# v6_net.net
KiCad netlist of a schematic drawn in Altium Designer
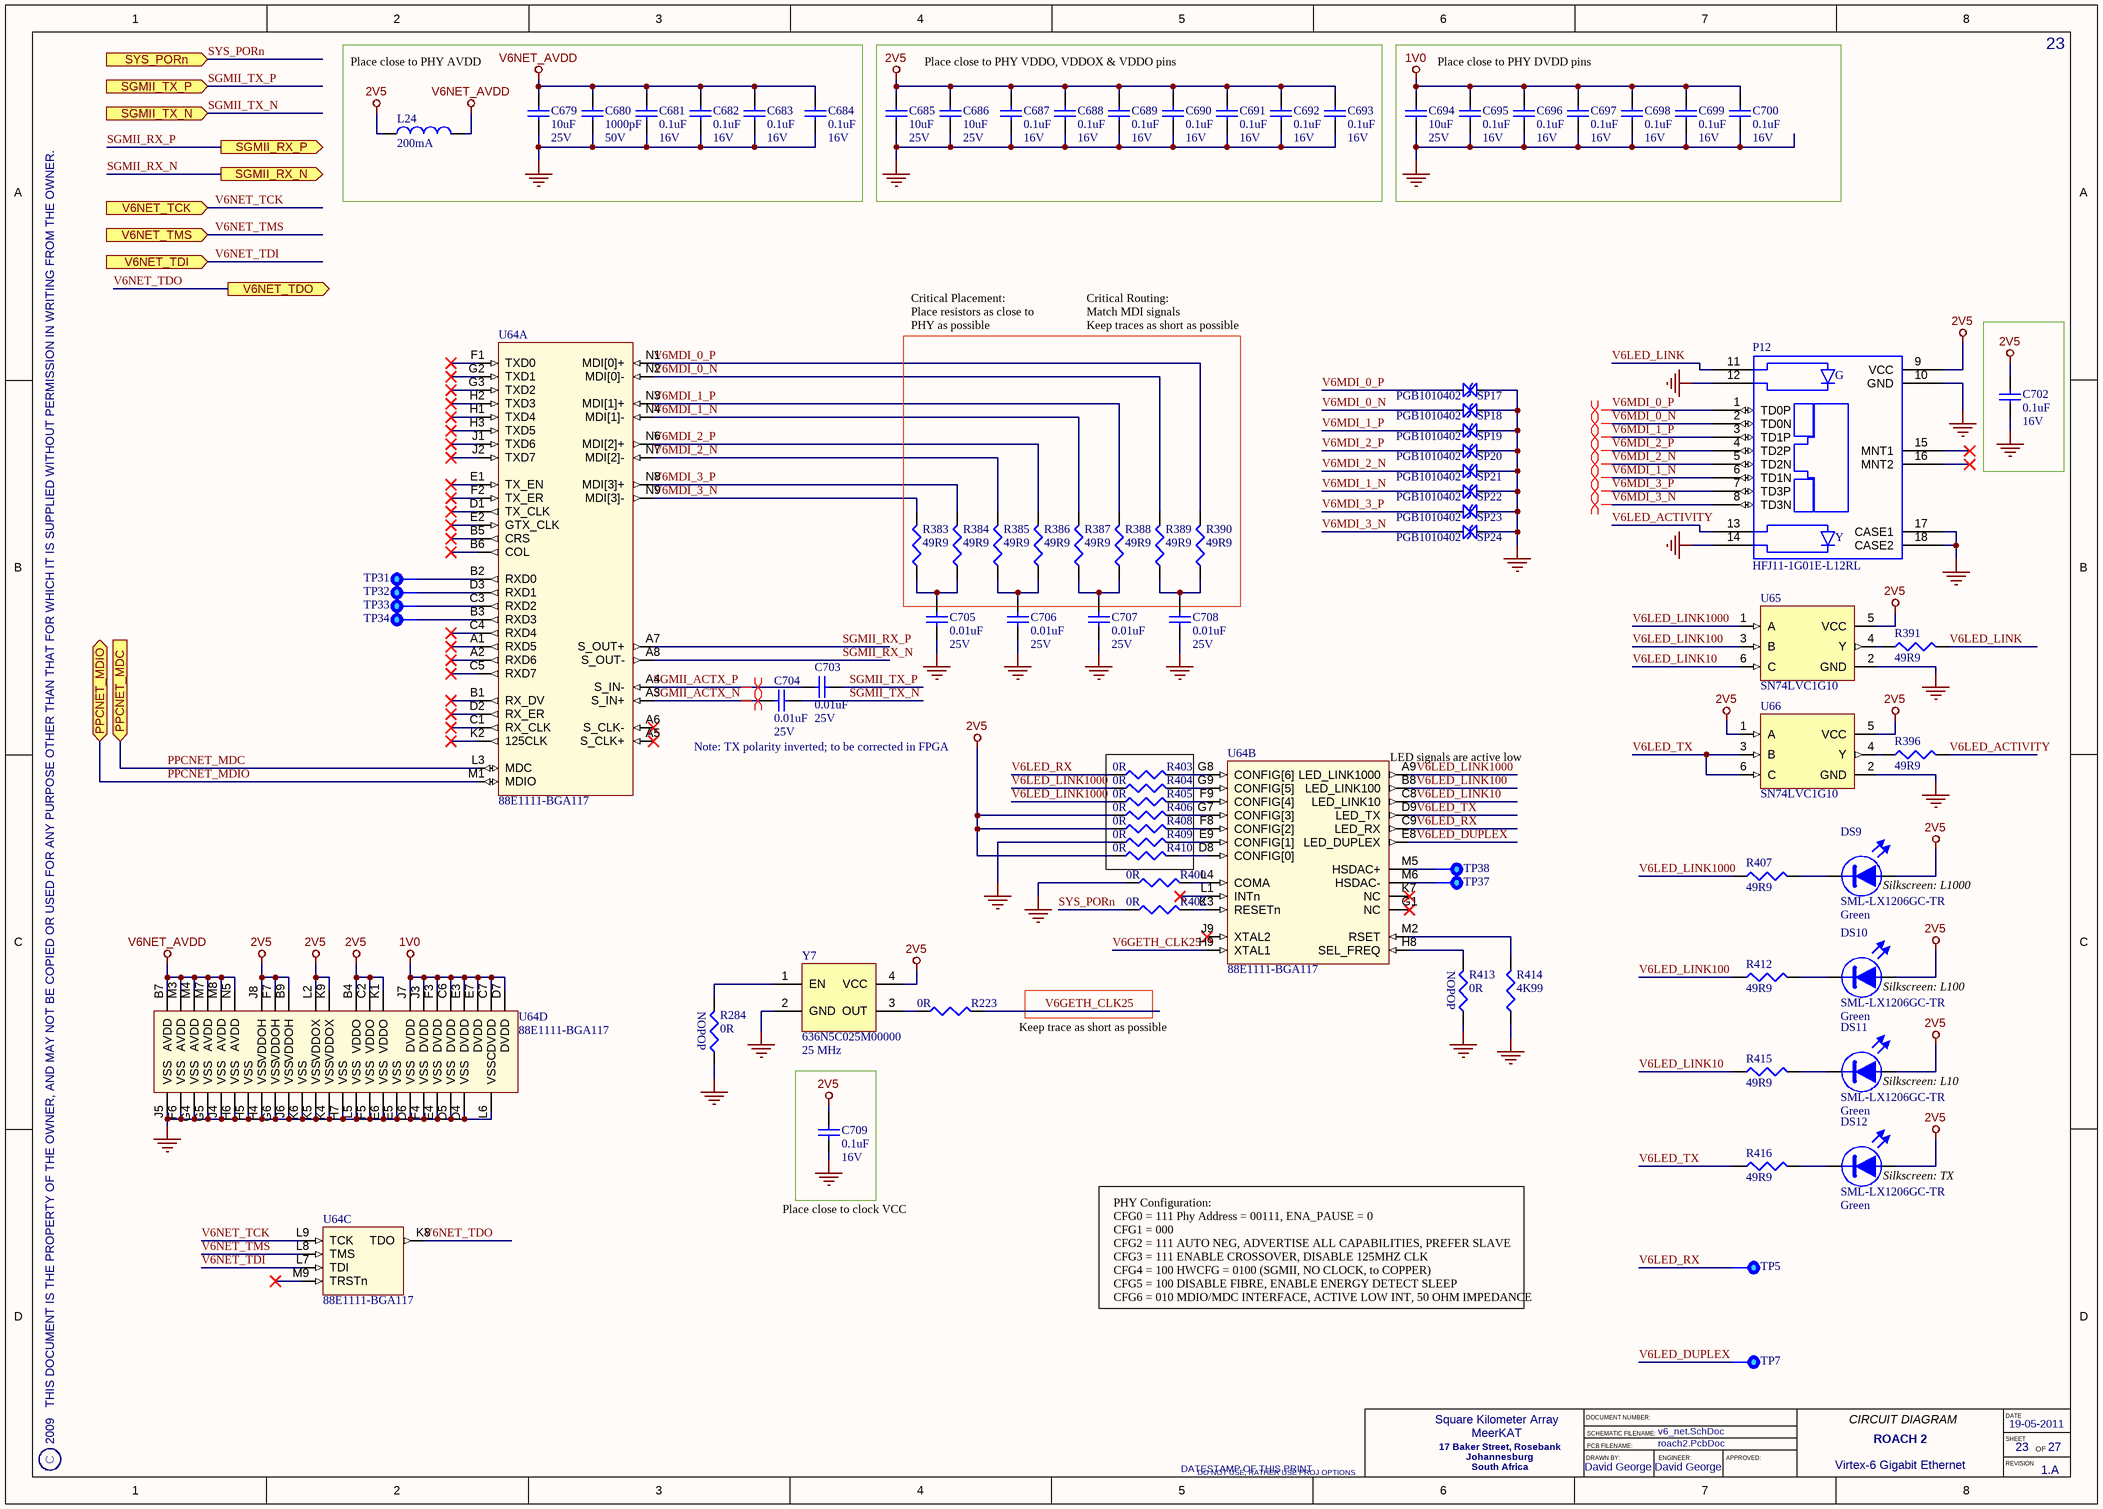
[diagram p0: v6_net.SchDoc]

(export (version "E")
  (design (tool "Eeschema 10.0.6"))
  (components
    (comp (ref "C679")
      (value "10uF")
      (footprint "CAPC3225X200L")
      (description "10uF, Ceramic Capacitor")
      (fields
        (field (name "RATING") "25V")
        (field (name "MANUFACTURER") "MURATA")
        (field (name "PARTNUM") "GRM32DR61E106KA12L")
      )
      (libsource (lib "altium_db") (part "CapStd"))
    )
    (comp (ref "C680")
      (value "1000pF")
      (footprint "CAPC1005X55L")
      (description "1000pF, Ceramic Capacitor")
      (fields
        (field (name "RATING") "50V")
        (field (name "MANUFACTURER") "MURATA")
        (field (name "PARTNUM") "GRM155R61H102KA01D")
      )
      (libsource (lib "altium_db") (part "CapStd"))
    )
    (comp (ref "C681")
      (value "0.1uF")
      (footprint "CAPC1005X60L")
      (description "0.1uF, Ceramic Capacitor")
      (fields
        (field (name "RATING") "16V")
        (field (name "MANUFACTURER") "VENKEL")
        (field (name "PARTNUM") "C0402X7R160-104KN")
      )
      (libsource (lib "altium_db") (part "CapStd"))
    )
    (comp (ref "C682")
      (value "0.1uF")
      (footprint "CAPC1005X60L")
      (description "0.1uF, Ceramic Capacitor")
      (fields
        (field (name "RATING") "16V")
        (field (name "MANUFACTURER") "VENKEL")
        (field (name "PARTNUM") "C0402X7R160-104KN")
      )
      (libsource (lib "altium_db") (part "CapStd"))
    )
    (comp (ref "C683")
      (value "0.1uF")
      (footprint "CAPC1005X60L")
      (description "0.1uF, Ceramic Capacitor")
      (fields
        (field (name "RATING") "16V")
        (field (name "MANUFACTURER") "VENKEL")
        (field (name "PARTNUM") "C0402X7R160-104KN")
      )
      (libsource (lib "altium_db") (part "CapStd"))
    )
    (comp (ref "C684")
      (value "0.1uF")
      (footprint "CAPC1005X60L")
      (description "0.1uF, Ceramic Capacitor")
      (fields
        (field (name "RATING") "16V")
        (field (name "MANUFACTURER") "VENKEL")
        (field (name "PARTNUM") "C0402X7R160-104KN")
      )
      (libsource (lib "altium_db") (part "CapStd"))
    )
    (comp (ref "C685")
      (value "10uF")
      (footprint "CAPC3225X200L")
      (description "10uF, Ceramic Capacitor")
      (fields
        (field (name "RATING") "25V")
        (field (name "MANUFACTURER") "MURATA")
        (field (name "PARTNUM") "GRM32DR61E106KA12L")
      )
      (libsource (lib "altium_db") (part "CapStd"))
    )
    (comp (ref "C686")
      (value "10uF")
      (footprint "CAPC3225X200L")
      (description "10uF, Ceramic Capacitor")
      (fields
        (field (name "RATING") "25V")
        (field (name "MANUFACTURER") "MURATA")
        (field (name "PARTNUM") "GRM32DR61E106KA12L")
      )
      (libsource (lib "altium_db") (part "CapStd"))
    )
    (comp (ref "C687")
      (value "0.1uF")
      (footprint "CAPC1005X60L")
      (description "0.1uF, Ceramic Capacitor")
      (fields
        (field (name "RATING") "16V")
        (field (name "MANUFACTURER") "VENKEL")
        (field (name "PARTNUM") "C0402X7R160-104KN")
      )
      (libsource (lib "altium_db") (part "CapStd"))
    )
    (comp (ref "C688")
      (value "0.1uF")
      (footprint "CAPC1005X60L")
      (description "0.1uF, Ceramic Capacitor")
      (fields
        (field (name "RATING") "16V")
        (field (name "MANUFACTURER") "VENKEL")
        (field (name "PARTNUM") "C0402X7R160-104KN")
      )
      (libsource (lib "altium_db") (part "CapStd"))
    )
    (comp (ref "C689")
      (value "0.1uF")
      (footprint "CAPC1005X60L")
      (description "0.1uF, Ceramic Capacitor")
      (fields
        (field (name "RATING") "16V")
        (field (name "MANUFACTURER") "VENKEL")
        (field (name "PARTNUM") "C0402X7R160-104KN")
      )
      (libsource (lib "altium_db") (part "CapStd"))
    )
    (comp (ref "C690")
      (value "0.1uF")
      (footprint "CAPC1005X60L")
      (description "0.1uF, Ceramic Capacitor")
      (fields
        (field (name "RATING") "16V")
        (field (name "MANUFACTURER") "VENKEL")
        (field (name "PARTNUM") "C0402X7R160-104KN")
      )
      (libsource (lib "altium_db") (part "CapStd"))
    )
    (comp (ref "C691")
      (value "0.1uF")
      (footprint "CAPC1005X60L")
      (description "0.1uF, Ceramic Capacitor")
      (fields
        (field (name "RATING") "16V")
        (field (name "MANUFACTURER") "VENKEL")
        (field (name "PARTNUM") "C0402X7R160-104KN")
      )
      (libsource (lib "altium_db") (part "CapStd"))
    )
    (comp (ref "C692")
      (value "0.1uF")
      (footprint "CAPC1005X60L")
      (description "0.1uF, Ceramic Capacitor")
      (fields
        (field (name "RATING") "16V")
        (field (name "MANUFACTURER") "VENKEL")
        (field (name "PARTNUM") "C0402X7R160-104KN")
      )
      (libsource (lib "altium_db") (part "CapStd"))
    )
    (comp (ref "C693")
      (value "0.1uF")
      (footprint "CAPC1005X60L")
      (description "0.1uF, Ceramic Capacitor")
      (fields
        (field (name "RATING") "16V")
        (field (name "MANUFACTURER") "VENKEL")
        (field (name "PARTNUM") "C0402X7R160-104KN")
      )
      (libsource (lib "altium_db") (part "CapStd"))
    )
    (comp (ref "C694")
      (value "10uF")
      (footprint "CAPC3225X200L")
      (description "10uF, Ceramic Capacitor")
      (fields
        (field (name "RATING") "25V")
        (field (name "MANUFACTURER") "MURATA")
        (field (name "PARTNUM") "GRM32DR61E106KA12L")
      )
      (libsource (lib "altium_db") (part "CapStd"))
    )
    (comp (ref "C695")
      (value "0.1uF")
      (footprint "CAPC1005X60L")
      (description "0.1uF, Ceramic Capacitor")
      (fields
        (field (name "RATING") "16V")
        (field (name "MANUFACTURER") "VENKEL")
        (field (name "PARTNUM") "C0402X7R160-104KN")
      )
      (libsource (lib "altium_db") (part "CapStd"))
    )
    (comp (ref "C696")
      (value "0.1uF")
      (footprint "CAPC1005X60L")
      (description "0.1uF, Ceramic Capacitor")
      (fields
        (field (name "RATING") "16V")
        (field (name "MANUFACTURER") "VENKEL")
        (field (name "PARTNUM") "C0402X7R160-104KN")
      )
      (libsource (lib "altium_db") (part "CapStd"))
    )
    (comp (ref "C697")
      (value "0.1uF")
      (footprint "CAPC1005X60L")
      (description "0.1uF, Ceramic Capacitor")
      (fields
        (field (name "RATING") "16V")
        (field (name "MANUFACTURER") "VENKEL")
        (field (name "PARTNUM") "C0402X7R160-104KN")
      )
      (libsource (lib "altium_db") (part "CapStd"))
    )
    (comp (ref "C698")
      (value "0.1uF")
      (footprint "CAPC1005X60L")
      (description "0.1uF, Ceramic Capacitor")
      (fields
        (field (name "RATING") "16V")
        (field (name "MANUFACTURER") "VENKEL")
        (field (name "PARTNUM") "C0402X7R160-104KN")
      )
      (libsource (lib "altium_db") (part "CapStd"))
    )
    (comp (ref "C699")
      (value "0.1uF")
      (footprint "CAPC1005X60L")
      (description "0.1uF, Ceramic Capacitor")
      (fields
        (field (name "RATING") "16V")
        (field (name "MANUFACTURER") "VENKEL")
        (field (name "PARTNUM") "C0402X7R160-104KN")
      )
      (libsource (lib "altium_db") (part "CapStd"))
    )
    (comp (ref "C700")
      (value "0.1uF")
      (footprint "CAPC1005X60L")
      (description "0.1uF, Ceramic Capacitor")
      (fields
        (field (name "RATING") "16V")
        (field (name "MANUFACTURER") "VENKEL")
        (field (name "PARTNUM") "C0402X7R160-104KN")
      )
      (libsource (lib "altium_db") (part "CapStd"))
    )
    (comp (ref "C702")
      (value "0.1uF")
      (footprint "CAPC1005X60L")
      (description "0.1uF, Ceramic Capacitor")
      (fields
        (field (name "RATING") "16V")
        (field (name "MANUFACTURER") "VENKEL")
        (field (name "PARTNUM") "C0402X7R160-104KN")
      )
      (libsource (lib "altium_db") (part "CapStd"))
    )
    (comp (ref "C703")
      (value "0.01uF")
      (footprint "CAPC1005X55L")
      (description "0.01uF, Ceramic Capacitor")
      (fields
        (field (name "RATING") "25V")
        (field (name "MANUFACTURER") "MURATA")
        (field (name "PARTNUM") "GRM155R71E103KA01D")
      )
      (libsource (lib "altium_db") (part "CapStd"))
    )
    (comp (ref "C704")
      (value "0.01uF")
      (footprint "CAPC1005X55L")
      (description "0.01uF, Ceramic Capacitor")
      (fields
        (field (name "RATING") "25V")
        (field (name "MANUFACTURER") "MURATA")
        (field (name "PARTNUM") "GRM155R71E103KA01D")
      )
      (libsource (lib "altium_db") (part "CapStd"))
    )
    (comp (ref "C705")
      (value "0.01uF")
      (footprint "CAPC1005X55L")
      (description "0.01uF, Ceramic Capacitor")
      (fields
        (field (name "RATING") "25V")
        (field (name "MANUFACTURER") "MURATA")
        (field (name "PARTNUM") "GRM155R71E103KA01D")
      )
      (libsource (lib "altium_db") (part "CapStd"))
    )
    (comp (ref "C706")
      (value "0.01uF")
      (footprint "CAPC1005X55L")
      (description "0.01uF, Ceramic Capacitor")
      (fields
        (field (name "RATING") "25V")
        (field (name "MANUFACTURER") "MURATA")
        (field (name "PARTNUM") "GRM155R71E103KA01D")
      )
      (libsource (lib "altium_db") (part "CapStd"))
    )
    (comp (ref "C707")
      (value "0.01uF")
      (footprint "CAPC1005X55L")
      (description "0.01uF, Ceramic Capacitor")
      (fields
        (field (name "RATING") "25V")
        (field (name "MANUFACTURER") "MURATA")
        (field (name "PARTNUM") "GRM155R71E103KA01D")
      )
      (libsource (lib "altium_db") (part "CapStd"))
    )
    (comp (ref "C708")
      (value "0.01uF")
      (footprint "CAPC1005X55L")
      (description "0.01uF, Ceramic Capacitor")
      (fields
        (field (name "RATING") "25V")
        (field (name "MANUFACTURER") "MURATA")
        (field (name "PARTNUM") "GRM155R71E103KA01D")
      )
      (libsource (lib "altium_db") (part "CapStd"))
    )
    (comp (ref "C709")
      (value "0.1uF")
      (footprint "CAPC1005X60L")
      (description "0.1uF, Ceramic Capacitor")
      (fields
        (field (name "RATING") "16V")
        (field (name "MANUFACTURER") "VENKEL")
        (field (name "PARTNUM") "C0402X7R160-104KN")
      )
      (libsource (lib "altium_db") (part "CapStd"))
    )
    (comp (ref "DS9")
      (value "SML-LX1206GC-TR")
      (footprint "LEDC3216X120N")
      (description "Green, Surface mount, LED, 1206")
      (fields (field (name "COLOUR") "Green") (field (name "MANUFACTURER") "LUMEX"))
      (libsource (lib "altium_db") (part "LEDSTD"))
    )
    (comp (ref "DS10")
      (value "SML-LX1206GC-TR")
      (footprint "LEDC3216X120N")
      (description "Green, Surface mount, LED, 1206")
      (fields (field (name "COLOUR") "Green") (field (name "MANUFACTURER") "LUMEX"))
      (libsource (lib "altium_db") (part "LEDSTD"))
    )
    (comp (ref "DS11")
      (value "SML-LX1206GC-TR")
      (footprint "LEDC3216X120N")
      (description "Green, Surface mount, LED, 1206")
      (fields (field (name "COLOUR") "Green") (field (name "MANUFACTURER") "LUMEX"))
      (libsource (lib "altium_db") (part "LEDSTD"))
    )
    (comp (ref "DS12")
      (value "SML-LX1206GC-TR")
      (footprint "LEDC3216X120N")
      (description "Green, Surface mount, LED, 1206")
      (fields (field (name "COLOUR") "Green") (field (name "MANUFACTURER") "LUMEX"))
      (libsource (lib "altium_db") (part "LEDSTD"))
    )
    (comp (ref "L24")
      (value "600R")
      (footprint "INDC2012X130L")
      (description "600 Ohm, Chip Ferrite Bead")
      (fields
        (field (name "RATING") "200mA")
        (field (name "MANUFACTURER") "Murata")
        (field (name "PARTNUM") "BLM21BD601SN1")
      )
      (libsource (lib "altium_db") (part "IndStd"))
    )
    (comp (ref "P12")
      (value "HFJ11-1G01E-L12RL")
      (footprint "HALO_HFJ11-1G02E-L55")
      (description "RJ45 with Integrated magnetic and dual LEDs")
      (fields (field (name "PARTNUM") "HFJ11-1G01E-L12RL") (field (name "MANUFACTURER") "HALO"))
      (libsource (lib "altium_db") (part "HFJ11-1G02E-L55"))
    )
    (comp (ref "R223")
      (value "0R")
      (footprint "RESC1005X40L")
      (description "0R, 1.1mm x 0.5mm, Thick Film Resistor")
      (fields (field (name "MANUFACTURER") "ROYALOHM") (field (name "PARTNUM") "0402WG00000T1E"))
      (libsource (lib "altium_db") (part "ResStd"))
    )
    (comp (ref "R284")
      (value "0R")
      (footprint "RESC1005X40L")
      (description "0R, 1.1mm x 0.5mm, Thick Film Resistor")
      (fields (field (name "MANUFACTURER") "ROYALOHM") (field (name "PARTNUM") "0402WG00000T1E"))
      (libsource (lib "altium_db") (part "ResStd"))
    )
    (comp (ref "R383")
      (value "49R9")
      (footprint "RESC1005X40L")
      (description "49R9, 1.1mm x 0.5mm, Thick Film Resistor")
      (fields (field (name "MANUFACTURER") "ROYALOHM") (field (name "PARTNUM") "0402WGF499JT1E"))
      (libsource (lib "altium_db") (part "ResStd"))
    )
    (comp (ref "R384")
      (value "49R9")
      (footprint "RESC1005X40L")
      (description "49R9, 1.1mm x 0.5mm, Thick Film Resistor")
      (fields (field (name "MANUFACTURER") "ROYALOHM") (field (name "PARTNUM") "0402WGF499JT1E"))
      (libsource (lib "altium_db") (part "ResStd"))
    )
    (comp (ref "R385")
      (value "49R9")
      (footprint "RESC1005X40L")
      (description "49R9, 1.1mm x 0.5mm, Thick Film Resistor")
      (fields (field (name "MANUFACTURER") "ROYALOHM") (field (name "PARTNUM") "0402WGF499JT1E"))
      (libsource (lib "altium_db") (part "ResStd"))
    )
    (comp (ref "R386")
      (value "49R9")
      (footprint "RESC1005X40L")
      (description "49R9, 1.1mm x 0.5mm, Thick Film Resistor")
      (fields (field (name "MANUFACTURER") "ROYALOHM") (field (name "PARTNUM") "0402WGF499JT1E"))
      (libsource (lib "altium_db") (part "ResStd"))
    )
    (comp (ref "R387")
      (value "49R9")
      (footprint "RESC1005X40L")
      (description "49R9, 1.1mm x 0.5mm, Thick Film Resistor")
      (fields (field (name "MANUFACTURER") "ROYALOHM") (field (name "PARTNUM") "0402WGF499JT1E"))
      (libsource (lib "altium_db") (part "ResStd"))
    )
    (comp (ref "R388")
      (value "49R9")
      (footprint "RESC1005X40L")
      (description "49R9, 1.1mm x 0.5mm, Thick Film Resistor")
      (fields (field (name "MANUFACTURER") "ROYALOHM") (field (name "PARTNUM") "0402WGF499JT1E"))
      (libsource (lib "altium_db") (part "ResStd"))
    )
    (comp (ref "R389")
      (value "49R9")
      (footprint "RESC1005X40L")
      (description "49R9, 1.1mm x 0.5mm, Thick Film Resistor")
      (fields (field (name "MANUFACTURER") "ROYALOHM") (field (name "PARTNUM") "0402WGF499JT1E"))
      (libsource (lib "altium_db") (part "ResStd"))
    )
    (comp (ref "R390")
      (value "49R9")
      (footprint "RESC1005X40L")
      (description "49R9, 1.1mm x 0.5mm, Thick Film Resistor")
      (fields (field (name "MANUFACTURER") "ROYALOHM") (field (name "PARTNUM") "0402WGF499JT1E"))
      (libsource (lib "altium_db") (part "ResStd"))
    )
    (comp (ref "R391")
      (value "49R9")
      (footprint "RESC1005X40L")
      (description "49R9, 1.1mm x 0.5mm, Thick Film Resistor")
      (fields (field (name "MANUFACTURER") "ROYALOHM") (field (name "PARTNUM") "0402WGF499JT1E"))
      (libsource (lib "altium_db") (part "ResStd"))
    )
    (comp (ref "R396")
      (value "49R9")
      (footprint "RESC1005X40L")
      (description "49R9, 1.1mm x 0.5mm, Thick Film Resistor")
      (fields (field (name "MANUFACTURER") "ROYALOHM") (field (name "PARTNUM") "0402WGF499JT1E"))
      (libsource (lib "altium_db") (part "ResStd"))
    )
    (comp (ref "R400")
      (value "0R")
      (footprint "RESC1005X40L")
      (description "0R, 1.1mm x 0.5mm, Thick Film Resistor")
      (fields (field (name "MANUFACTURER") "ROYALOHM") (field (name "PARTNUM") "0402WG00000T1E"))
      (libsource (lib "altium_db") (part "ResStd"))
    )
    (comp (ref "R402")
      (value "0R")
      (footprint "RESC1005X40L")
      (description "0R, 1.1mm x 0.5mm, Thick Film Resistor")
      (fields (field (name "MANUFACTURER") "ROYALOHM") (field (name "PARTNUM") "0402WG00000T1E"))
      (libsource (lib "altium_db") (part "ResStd"))
    )
    (comp (ref "R403")
      (value "0R")
      (footprint "RESC1005X40L")
      (description "0R, 1.1mm x 0.5mm, Thick Film Resistor")
      (fields (field (name "MANUFACTURER") "ROYALOHM") (field (name "PARTNUM") "0402WG00000T1E"))
      (libsource (lib "altium_db") (part "ResStd"))
    )
    (comp (ref "R404")
      (value "0R")
      (footprint "RESC1005X40L")
      (description "0R, 1.1mm x 0.5mm, Thick Film Resistor")
      (fields (field (name "MANUFACTURER") "ROYALOHM") (field (name "PARTNUM") "0402WG00000T1E"))
      (libsource (lib "altium_db") (part "ResStd"))
    )
    (comp (ref "R405")
      (value "0R")
      (footprint "RESC1005X40L")
      (description "0R, 1.1mm x 0.5mm, Thick Film Resistor")
      (fields (field (name "MANUFACTURER") "ROYALOHM") (field (name "PARTNUM") "0402WG00000T1E"))
      (libsource (lib "altium_db") (part "ResStd"))
    )
    (comp (ref "R406")
      (value "0R")
      (footprint "RESC1005X40L")
      (description "0R, 1.1mm x 0.5mm, Thick Film Resistor")
      (fields (field (name "MANUFACTURER") "ROYALOHM") (field (name "PARTNUM") "0402WG00000T1E"))
      (libsource (lib "altium_db") (part "ResStd"))
    )
    (comp (ref "R407")
      (value "49R9")
      (footprint "RESC1005X40L")
      (description "49R9, 1.1mm x 0.5mm, Thick Film Resistor")
      (fields (field (name "MANUFACTURER") "ROYALOHM") (field (name "PARTNUM") "0402WGF499JT1E"))
      (libsource (lib "altium_db") (part "ResStd"))
    )
    (comp (ref "R408")
      (value "0R")
      (footprint "RESC1005X40L")
      (description "0R, 1.1mm x 0.5mm, Thick Film Resistor")
      (fields (field (name "MANUFACTURER") "ROYALOHM") (field (name "PARTNUM") "0402WG00000T1E"))
      (libsource (lib "altium_db") (part "ResStd"))
    )
    (comp (ref "R409")
      (value "0R")
      (footprint "RESC1005X40L")
      (description "0R, 1.1mm x 0.5mm, Thick Film Resistor")
      (fields (field (name "MANUFACTURER") "ROYALOHM") (field (name "PARTNUM") "0402WG00000T1E"))
      (libsource (lib "altium_db") (part "ResStd"))
    )
    (comp (ref "R410")
      (value "0R")
      (footprint "RESC1005X40L")
      (description "0R, 1.1mm x 0.5mm, Thick Film Resistor")
      (fields (field (name "MANUFACTURER") "ROYALOHM") (field (name "PARTNUM") "0402WG00000T1E"))
      (libsource (lib "altium_db") (part "ResStd"))
    )
    (comp (ref "R412")
      (value "49R9")
      (footprint "RESC1005X40L")
      (description "49R9, 1.1mm x 0.5mm, Thick Film Resistor")
      (fields (field (name "MANUFACTURER") "ROYALOHM") (field (name "PARTNUM") "0402WGF499JT1E"))
      (libsource (lib "altium_db") (part "ResStd"))
    )
    (comp (ref "R413")
      (value "0R")
      (footprint "RESC1005X40L")
      (description "0R, 1.1mm x 0.5mm, Thick Film Resistor")
      (fields (field (name "MANUFACTURER") "ROYALOHM") (field (name "PARTNUM") "0402WG00000T1E"))
      (libsource (lib "altium_db") (part "ResStd"))
    )
    (comp (ref "R414")
      (value "4K99")
      (footprint "RESC1005X40L")
      (description "4K99, 1.1mm x 0.5mm, Thick Film Resistor")
      (fields (field (name "MANUFACTURER") "ROYALOHM") (field (name "PARTNUM") "0402WGF4991T1E"))
      (libsource (lib "altium_db") (part "ResStd"))
    )
    (comp (ref "R415")
      (value "49R9")
      (footprint "RESC1005X40L")
      (description "49R9, 1.1mm x 0.5mm, Thick Film Resistor")
      (fields (field (name "MANUFACTURER") "ROYALOHM") (field (name "PARTNUM") "0402WGF499JT1E"))
      (libsource (lib "altium_db") (part "ResStd"))
    )
    (comp (ref "R416")
      (value "49R9")
      (footprint "RESC1005X40L")
      (description "49R9, 1.1mm x 0.5mm, Thick Film Resistor")
      (fields (field (name "MANUFACTURER") "ROYALOHM") (field (name "PARTNUM") "0402WGF499JT1E"))
      (libsource (lib "altium_db") (part "ResStd"))
    )
    (comp (ref "SP17")
      (value "PGB1010402")
      (footprint "PGB1010402")
      (description "Surface Mount Polymeric ESD Suppressor in an 0402 package")
      (fields (field (name "PARTNUM") "PGB1010402"))
      (libsource (lib "altium_db") (part "PGB1010402"))
    )
    (comp (ref "SP18")
      (value "PGB1010402")
      (footprint "PGB1010402")
      (description "Surface Mount Polymeric ESD Suppressor in an 0402 package")
      (fields (field (name "PARTNUM") "PGB1010402"))
      (libsource (lib "altium_db") (part "PGB1010402"))
    )
    (comp (ref "SP19")
      (value "PGB1010402")
      (footprint "PGB1010402")
      (description "Surface Mount Polymeric ESD Suppressor in an 0402 package")
      (fields (field (name "PARTNUM") "PGB1010402"))
      (libsource (lib "altium_db") (part "PGB1010402"))
    )
    (comp (ref "SP20")
      (value "PGB1010402")
      (footprint "PGB1010402")
      (description "Surface Mount Polymeric ESD Suppressor in an 0402 package")
      (fields (field (name "PARTNUM") "PGB1010402"))
      (libsource (lib "altium_db") (part "PGB1010402"))
    )
    (comp (ref "SP21")
      (value "PGB1010402")
      (footprint "PGB1010402")
      (description "Surface Mount Polymeric ESD Suppressor in an 0402 package")
      (fields (field (name "PARTNUM") "PGB1010402"))
      (libsource (lib "altium_db") (part "PGB1010402"))
    )
    (comp (ref "SP22")
      (value "PGB1010402")
      (footprint "PGB1010402")
      (description "Surface Mount Polymeric ESD Suppressor in an 0402 package")
      (fields (field (name "PARTNUM") "PGB1010402"))
      (libsource (lib "altium_db") (part "PGB1010402"))
    )
    (comp (ref "SP23")
      (value "PGB1010402")
      (footprint "PGB1010402")
      (description "Surface Mount Polymeric ESD Suppressor in an 0402 package")
      (fields (field (name "PARTNUM") "PGB1010402"))
      (libsource (lib "altium_db") (part "PGB1010402"))
    )
    (comp (ref "SP24")
      (value "PGB1010402")
      (footprint "PGB1010402")
      (description "Surface Mount Polymeric ESD Suppressor in an 0402 package")
      (fields (field (name "PARTNUM") "PGB1010402"))
      (libsource (lib "altium_db") (part "PGB1010402"))
    )
    (comp (ref "TP5")
      (value "Testpoint")
      (footprint "TP100")
      (description "1mm Diameter, through-hole, Circular Test-point")
      (libsource (lib "altium_db") (part "Testpoint"))
    )
    (comp (ref "TP7")
      (value "Testpoint")
      (footprint "TP100")
      (description "1mm Diameter, through-hole, Circular Test-point")
      (libsource (lib "altium_db") (part "Testpoint"))
    )
    (comp (ref "TP31")
      (value "Testpoint")
      (footprint "TP100")
      (description "1mm Diameter, through-hole, Circular Test-point")
      (libsource (lib "altium_db") (part "Testpoint"))
    )
    (comp (ref "TP32")
      (value "Testpoint")
      (footprint "TP100")
      (description "1mm Diameter, through-hole, Circular Test-point")
      (libsource (lib "altium_db") (part "Testpoint"))
    )
    (comp (ref "TP33")
      (value "Testpoint")
      (footprint "TP100")
      (description "1mm Diameter, through-hole, Circular Test-point")
      (libsource (lib "altium_db") (part "Testpoint"))
    )
    (comp (ref "TP34")
      (value "Testpoint")
      (footprint "TP100")
      (description "1mm Diameter, through-hole, Circular Test-point")
      (libsource (lib "altium_db") (part "Testpoint"))
    )
    (comp (ref "TP37")
      (value "Testpoint")
      (footprint "TP100")
      (description "1mm Diameter, through-hole, Circular Test-point")
      (libsource (lib "altium_db") (part "Testpoint"))
    )
    (comp (ref "TP38")
      (value "Testpoint")
      (footprint "TP100")
      (description "1mm Diameter, through-hole, Circular Test-point")
      (libsource (lib "altium_db") (part "Testpoint"))
    )
    (comp (ref "U64")
      (value "88E1111-BGA117")
      (footprint "BGA117C100P13X9_1400X1000X154")
      (description "Integrated 10/100/1000 Ultra Gigabit Ethernet Transceiver")
      (fields (field (name "MANUFACTURER") "Marvell") (field (name "PARTNUM") "88E1111-XX-BAB1C000"))
      (libsource (lib "altium_db") (part "88E1111-TFBGA117"))
    )
    (comp (ref "U65")
      (value "SN74LVC1G10")
      (footprint "SOT23-6")
      (description "Single 3-input Positive-NAND gate")
      (fields (field (name "MANUFACTURER") "Texas Instruments"))
      (libsource (lib "altium_db") (part "SN74LVC1G10"))
    )
    (comp (ref "U66")
      (value "SN74LVC1G10")
      (footprint "SOT23-6")
      (description "Single 3-input Positive-NAND gate")
      (fields (field (name "MANUFACTURER") "Texas Instruments"))
      (libsource (lib "altium_db") (part "SN74LVC1G10"))
    )
    (comp (ref "Y7")
      (value "636N5C025M00000")
      (footprint "636XXXXXXMXXXXX")
      (description "25.00 MHz, 2V5, CTS 636 clock oscillator")
      (fields
        (field (name "PARTNUM") "636N5C025M00000")
        (field (name "FREQUENCY") "25 MHz")
        (field (name "MANUFACTURER") "CTS")
      )
      (libsource (lib "altium_db") (part "636XXXXXXMXXXXX"))
    )
  )
  (nets
    (net (code "1") (name "/PPCNET_MDC") (class "Default")
      (node (ref "U64") (pin "L3") (pinfunction "MDC_L3") (pintype "bidirectional"))
    )
    (net (code "2") (name "/PPCNET_MDIO") (class "Default")
      (node (ref "U64") (pin "M1") (pinfunction "MDIO_M1") (pintype "bidirectional"))
    )
    (net (code "3") (name "/SGMII_ACTX_N") (class "Default")
      (node (ref "C704") (pin "2") (pinfunction "2_2") (pintype "passive"))
      (node (ref "U64") (pin "A3") (pinfunction "S_IN+_A3") (pintype "input"))
    )
    (net (code "4") (name "/SGMII_ACTX_P") (class "Default")
      (node (ref "C703") (pin "2") (pinfunction "2_2") (pintype "passive"))
      (node (ref "U64") (pin "A4") (pinfunction "S_IN-_A4") (pintype "input"))
    )
    (net (code "5") (name "/SGMII_RX_N") (class "Default")
      (node (ref "U64") (pin "A8") (pinfunction "S_OUT-_A8") (pintype "output"))
    )
    (net (code "6") (name "/SGMII_RX_P") (class "Default")
      (node (ref "U64") (pin "A7") (pinfunction "S_OUT+_A7") (pintype "output"))
    )
    (net (code "7") (name "/SGMII_TX_N") (class "Default")
      (node (ref "C704") (pin "1") (pinfunction "1_1") (pintype "passive"))
    )
    (net (code "8") (name "/SGMII_TX_P") (class "Default")
      (node (ref "C703") (pin "1") (pinfunction "1_1") (pintype "passive"))
    )
    (net (code "9") (name "/SYS_PORn") (class "Default")
      (node (ref "R402") (pin "1") (pinfunction "1_1") (pintype "passive"))
    )
    (net (code "10") (name "/V6GETH_CLK25") (class "Default")
      (node (ref "R223") (pin "2") (pinfunction "2_2") (pintype "passive"))
      (node (ref "U64") (pin "H9") (pinfunction "XTAL1_H9") (pintype "input"))
    )
    (net (code "11") (name "/V6LED_ACTIVITY") (class "Default")
      (node (ref "P12") (pin "13") (pinfunction "L1_YC_GA_13") (pintype "passive"))
      (node (ref "R396") (pin "2") (pinfunction "2_2") (pintype "passive"))
    )
    (net (code "12") (name "/V6LED_DUPLEX") (class "Default")
      (node (ref "TP7") (pin "1") (pinfunction "1_1") (pintype "passive"))
      (node (ref "U64") (pin "E8") (pinfunction "LED_DUPLEX_E8") (pintype "output"))
    )
    (net (code "13") (name "/V6LED_LINK") (class "Default")
      (node (ref "P12") (pin "11") (pinfunction "R1_YC_GA_11") (pintype "passive"))
      (node (ref "R391") (pin "2") (pinfunction "2_2") (pintype "passive"))
    )
    (net (code "14") (name "/V6LED_LINK10") (class "Default")
      (node (ref "R415") (pin "1") (pinfunction "1_1") (pintype "passive"))
      (node (ref "U64") (pin "C8") (pinfunction "LED_LINK10_C8") (pintype "output"))
      (node (ref "U65") (pin "6") (pinfunction "C_6") (pintype "input"))
    )
    (net (code "15") (name "/V6LED_LINK100") (class "Default")
      (node (ref "R412") (pin "1") (pinfunction "1_1") (pintype "passive"))
      (node (ref "U64") (pin "B8") (pinfunction "LED_LINK100_B8") (pintype "output"))
      (node (ref "U65") (pin "3") (pinfunction "B_3") (pintype "input"))
    )
    (net (code "16") (name "/V6LED_LINK1000") (class "Default")
      (node (ref "R404") (pin "1") (pinfunction "1_1") (pintype "passive"))
      (node (ref "R405") (pin "1") (pinfunction "1_1") (pintype "passive"))
      (node (ref "R407") (pin "1") (pinfunction "1_1") (pintype "passive"))
      (node (ref "U64") (pin "A9") (pinfunction "LED_LINK1000_A9") (pintype "output"))
      (node (ref "U65") (pin "1") (pinfunction "A_1") (pintype "input"))
    )
    (net (code "17") (name "/V6LED_RX") (class "Default")
      (node (ref "R403") (pin "1") (pinfunction "1_1") (pintype "passive"))
      (node (ref "TP5") (pin "1") (pinfunction "1_1") (pintype "passive"))
      (node (ref "U64") (pin "C9") (pinfunction "LED_RX_C9") (pintype "output"))
    )
    (net (code "18") (name "/V6LED_TX") (class "Default")
      (node (ref "R416") (pin "1") (pinfunction "1_1") (pintype "passive"))
      (node (ref "U64") (pin "D9") (pinfunction "LED_TX_D9") (pintype "output"))
      (node (ref "U66") (pin "3") (pinfunction "B_3") (pintype "input"))
      (node (ref "U66") (pin "6") (pinfunction "C_6") (pintype "input"))
    )
    (net (code "19") (name "/V6MDI_0_N") (class "Default")
      (node (ref "P12") (pin "2") (pinfunction "TD0N_2") (pintype "bidirectional"))
      (node (ref "R389") (pin "2") (pinfunction "2_2") (pintype "passive"))
      (node (ref "SP18") (pin "2") (pinfunction "B_2") (pintype "passive"))
      (node (ref "U64") (pin "N2") (pinfunction "MDI[0]-_N2") (pintype "input"))
    )
    (net (code "20") (name "/V6MDI_0_P") (class "Default")
      (node (ref "P12") (pin "1") (pinfunction "TD0P_1") (pintype "bidirectional"))
      (node (ref "R390") (pin "2") (pinfunction "2_2") (pintype "passive"))
      (node (ref "SP17") (pin "2") (pinfunction "B_2") (pintype "passive"))
      (node (ref "U64") (pin "N1") (pinfunction "MDI[0]+_N1") (pintype "input"))
    )
    (net (code "21") (name "/V6MDI_1_N") (class "Default")
      (node (ref "P12") (pin "6") (pinfunction "TD1N_6") (pintype "bidirectional"))
      (node (ref "R387") (pin "2") (pinfunction "2_2") (pintype "passive"))
      (node (ref "SP22") (pin "2") (pinfunction "B_2") (pintype "passive"))
      (node (ref "U64") (pin "N4") (pinfunction "MDI[1]-_N4") (pintype "input"))
    )
    (net (code "22") (name "/V6MDI_1_P") (class "Default")
      (node (ref "P12") (pin "3") (pinfunction "TD1P_3") (pintype "bidirectional"))
      (node (ref "R388") (pin "2") (pinfunction "2_2") (pintype "passive"))
      (node (ref "SP19") (pin "2") (pinfunction "B_2") (pintype "passive"))
      (node (ref "U64") (pin "N3") (pinfunction "MDI[1]+_N3") (pintype "input"))
    )
    (net (code "23") (name "/V6MDI_2_N") (class "Default")
      (node (ref "P12") (pin "5") (pinfunction "TD2N_5") (pintype "bidirectional"))
      (node (ref "R385") (pin "2") (pinfunction "2_2") (pintype "passive"))
      (node (ref "SP21") (pin "2") (pinfunction "B_2") (pintype "passive"))
      (node (ref "U64") (pin "N7") (pinfunction "MDI[2]-_N7") (pintype "input"))
    )
    (net (code "24") (name "/V6MDI_2_P") (class "Default")
      (node (ref "P12") (pin "4") (pinfunction "TD2P_4") (pintype "bidirectional"))
      (node (ref "R386") (pin "2") (pinfunction "2_2") (pintype "passive"))
      (node (ref "SP20") (pin "2") (pinfunction "B_2") (pintype "passive"))
      (node (ref "U64") (pin "N6") (pinfunction "MDI[2]+_N6") (pintype "output"))
    )
    (net (code "25") (name "/V6MDI_3_N") (class "Default")
      (node (ref "P12") (pin "8") (pinfunction "TD3N_8") (pintype "bidirectional"))
      (node (ref "R383") (pin "2") (pinfunction "2_2") (pintype "passive"))
      (node (ref "SP24") (pin "2") (pinfunction "B_2") (pintype "passive"))
      (node (ref "U64") (pin "N9") (pinfunction "MDI[3]-_N9") (pintype "output"))
    )
    (net (code "26") (name "/V6MDI_3_P") (class "Default")
      (node (ref "P12") (pin "7") (pinfunction "TD3P_7") (pintype "bidirectional"))
      (node (ref "R384") (pin "2") (pinfunction "2_2") (pintype "passive"))
      (node (ref "SP23") (pin "2") (pinfunction "B_2") (pintype "passive"))
      (node (ref "U64") (pin "N8") (pinfunction "MDI[3]+_N8") (pintype "output"))
    )
    (net (code "27") (name "/V6NET_TCK") (class "Default")
      (node (ref "U64") (pin "L9") (pinfunction "TCK_L9") (pintype "input"))
    )
    (net (code "28") (name "/V6NET_TDI") (class "Default")
      (node (ref "U64") (pin "L7") (pinfunction "TDI_L7") (pintype "input"))
    )
    (net (code "29") (name "/V6NET_TDO") (class "Default")
      (node (ref "U64") (pin "K8") (pinfunction "TDO_K8") (pintype "output"))
    )
    (net (code "30") (name "/V6NET_TMS") (class "Default")
      (node (ref "U64") (pin "L8") (pinfunction "TMS_L8") (pintype "input"))
    )
    (net (code "31") (name "1V0") (class "Default")
      (node (ref "C694") (pin "2") (pinfunction "2_2") (pintype "passive"))
      (node (ref "C695") (pin "2") (pinfunction "2_2") (pintype "passive"))
      (node (ref "C696") (pin "2") (pinfunction "2_2") (pintype "passive"))
      (node (ref "C697") (pin "2") (pinfunction "2_2") (pintype "passive"))
      (node (ref "C698") (pin "2") (pinfunction "2_2") (pintype "passive"))
      (node (ref "C699") (pin "2") (pinfunction "2_2") (pintype "passive"))
      (node (ref "C700") (pin "2") (pinfunction "2_2") (pintype "passive"))
      (node (ref "U64") (pin "C6") (pinfunction "DVDD_C6") (pintype "power_in"))
      (node (ref "U64") (pin "C7") (pinfunction "DVDD_C7") (pintype "power_in"))
      (node (ref "U64") (pin "D7") (pinfunction "DVDD_D7") (pintype "power_in"))
      (node (ref "U64") (pin "E3") (pinfunction "DVDD_E3") (pintype "power_in"))
      (node (ref "U64") (pin "E7") (pinfunction "DVDD_E7") (pintype "power_in"))
      (node (ref "U64") (pin "F3") (pinfunction "DVDD_F3") (pintype "power_in"))
      (node (ref "U64") (pin "J3") (pinfunction "DVDD_J3") (pintype "power_in"))
      (node (ref "U64") (pin "J7") (pinfunction "DVDD_J7") (pintype "power_in"))
    )
    (net (code "32") (name "2V5") (class "Default")
      (node (ref "C685") (pin "2") (pinfunction "2_2") (pintype "passive"))
      (node (ref "C686") (pin "2") (pinfunction "2_2") (pintype "passive"))
      (node (ref "C687") (pin "2") (pinfunction "2_2") (pintype "passive"))
      (node (ref "C688") (pin "2") (pinfunction "2_2") (pintype "passive"))
      (node (ref "C689") (pin "2") (pinfunction "2_2") (pintype "passive"))
      (node (ref "C690") (pin "2") (pinfunction "2_2") (pintype "passive"))
      (node (ref "C691") (pin "2") (pinfunction "2_2") (pintype "passive"))
      (node (ref "C692") (pin "2") (pinfunction "2_2") (pintype "passive"))
      (node (ref "C693") (pin "2") (pinfunction "2_2") (pintype "passive"))
      (node (ref "C702") (pin "2") (pinfunction "2_2") (pintype "passive"))
      (node (ref "C709") (pin "2") (pinfunction "2_2") (pintype "passive"))
      (node (ref "DS10") (pin "2") (pinfunction "A_2") (pintype "passive"))
      (node (ref "DS11") (pin "2") (pinfunction "A_2") (pintype "passive"))
      (node (ref "DS12") (pin "2") (pinfunction "A_2") (pintype "passive"))
      (node (ref "DS9") (pin "2") (pinfunction "A_2") (pintype "passive"))
      (node (ref "L24") (pin "1") (pinfunction "1_1") (pintype "passive"))
      (node (ref "P12") (pin "9") (pinfunction "VCC_9") (pintype "power_in"))
      (node (ref "R406") (pin "1") (pinfunction "1_1") (pintype "passive"))
      (node (ref "R408") (pin "1") (pinfunction "1_1") (pintype "passive"))
      (node (ref "R410") (pin "1") (pinfunction "1_1") (pintype "passive"))
      (node (ref "U64") (pin "B4") (pinfunction "VDDO_B4") (pintype "power_in"))
      (node (ref "U64") (pin "B9") (pinfunction "VDDOH_B9") (pintype "power_in"))
      (node (ref "U64") (pin "C2") (pinfunction "VDDO_C2") (pintype "power_in"))
      (node (ref "U64") (pin "F7") (pinfunction "VDDOH_F7") (pintype "power_in"))
      (node (ref "U64") (pin "J8") (pinfunction "VDDOH_J8") (pintype "power_in"))
      (node (ref "U64") (pin "K1") (pinfunction "VDDO_K1") (pintype "power_in"))
      (node (ref "U64") (pin "K9") (pinfunction "VDDOX_K9") (pintype "power_in"))
      (node (ref "U64") (pin "L2") (pinfunction "VDDOX_L2") (pintype "power_in"))
      (node (ref "U65") (pin "5") (pinfunction "VCC_5") (pintype "power_in"))
      (node (ref "U66") (pin "1") (pinfunction "A_1") (pintype "input"))
      (node (ref "U66") (pin "5") (pinfunction "VCC_5") (pintype "power_in"))
      (node (ref "Y7") (pin "4") (pinfunction "VCC_4") (pintype "passive"))
    )
    (net (code "33") (name "GND") (class "Default")
      (node (ref "C679") (pin "1") (pinfunction "1_1") (pintype "passive"))
      (node (ref "C680") (pin "1") (pinfunction "1_1") (pintype "passive"))
      (node (ref "C681") (pin "1") (pinfunction "1_1") (pintype "passive"))
      (node (ref "C682") (pin "1") (pinfunction "1_1") (pintype "passive"))
      (node (ref "C683") (pin "1") (pinfunction "1_1") (pintype "passive"))
      (node (ref "C684") (pin "1") (pinfunction "1_1") (pintype "passive"))
      (node (ref "C685") (pin "1") (pinfunction "1_1") (pintype "passive"))
      (node (ref "C686") (pin "1") (pinfunction "1_1") (pintype "passive"))
      (node (ref "C687") (pin "1") (pinfunction "1_1") (pintype "passive"))
      (node (ref "C688") (pin "1") (pinfunction "1_1") (pintype "passive"))
      (node (ref "C689") (pin "1") (pinfunction "1_1") (pintype "passive"))
      (node (ref "C690") (pin "1") (pinfunction "1_1") (pintype "passive"))
      (node (ref "C691") (pin "1") (pinfunction "1_1") (pintype "passive"))
      (node (ref "C692") (pin "1") (pinfunction "1_1") (pintype "passive"))
      (node (ref "C693") (pin "1") (pinfunction "1_1") (pintype "passive"))
      (node (ref "C694") (pin "1") (pinfunction "1_1") (pintype "passive"))
      (node (ref "C695") (pin "1") (pinfunction "1_1") (pintype "passive"))
      (node (ref "C696") (pin "1") (pinfunction "1_1") (pintype "passive"))
      (node (ref "C697") (pin "1") (pinfunction "1_1") (pintype "passive"))
      (node (ref "C698") (pin "1") (pinfunction "1_1") (pintype "passive"))
      (node (ref "C699") (pin "1") (pinfunction "1_1") (pintype "passive"))
      (node (ref "C700") (pin "1") (pinfunction "1_1") (pintype "passive"))
      (node (ref "C702") (pin "1") (pinfunction "1_1") (pintype "passive"))
      (node (ref "C705") (pin "2") (pinfunction "2_2") (pintype "passive"))
      (node (ref "C706") (pin "2") (pinfunction "2_2") (pintype "passive"))
      (node (ref "C707") (pin "2") (pinfunction "2_2") (pintype "passive"))
      (node (ref "C708") (pin "2") (pinfunction "2_2") (pintype "passive"))
      (node (ref "C709") (pin "1") (pinfunction "1_1") (pintype "passive"))
      (node (ref "P12") (pin "10") (pinfunction "GND_10") (pintype "power_in"))
      (node (ref "P12") (pin "12") (pinfunction "R1_YA_GC_12") (pintype "passive"))
      (node (ref "P12") (pin "14") (pinfunction "L1_YA_GC_14") (pintype "passive"))
      (node (ref "P12") (pin "17") (pinfunction "CASE1_17") (pintype "power_in"))
      (node (ref "P12") (pin "18") (pinfunction "CASE2_18") (pintype "power_in"))
      (node (ref "R284") (pin "1") (pinfunction "1_1") (pintype "passive"))
      (node (ref "R400") (pin "1") (pinfunction "1_1") (pintype "passive"))
      (node (ref "R409") (pin "1") (pinfunction "1_1") (pintype "passive"))
      (node (ref "R413") (pin "1") (pinfunction "1_1") (pintype "passive"))
      (node (ref "R414") (pin "1") (pinfunction "1_1") (pintype "passive"))
      (node (ref "SP17") (pin "1") (pinfunction "A_1") (pintype "passive"))
      (node (ref "SP18") (pin "1") (pinfunction "A_1") (pintype "passive"))
      (node (ref "SP19") (pin "1") (pinfunction "A_1") (pintype "passive"))
      (node (ref "SP20") (pin "1") (pinfunction "A_1") (pintype "passive"))
      (node (ref "SP21") (pin "1") (pinfunction "A_1") (pintype "passive"))
      (node (ref "SP22") (pin "1") (pinfunction "A_1") (pintype "passive"))
      (node (ref "SP23") (pin "1") (pinfunction "A_1") (pintype "passive"))
      (node (ref "SP24") (pin "1") (pinfunction "A_1") (pintype "passive"))
      (node (ref "U64") (pin "D4") (pinfunction "VSS_D4") (pintype "power_in"))
      (node (ref "U64") (pin "D5") (pinfunction "VSS_D5") (pintype "power_in"))
      (node (ref "U64") (pin "D6") (pinfunction "VSS_D6") (pintype "power_in"))
      (node (ref "U64") (pin "E4") (pinfunction "VSS_E4") (pintype "power_in"))
      (node (ref "U64") (pin "E5") (pinfunction "VSS_E5") (pintype "power_in"))
      (node (ref "U64") (pin "E6") (pinfunction "VSS_E6") (pintype "power_in"))
      (node (ref "U64") (pin "F4") (pinfunction "VSS_F4") (pintype "power_in"))
      (node (ref "U64") (pin "F5") (pinfunction "VSS_F5") (pintype "power_in"))
      (node (ref "U64") (pin "F6") (pinfunction "VSS_F6") (pintype "power_in"))
      (node (ref "U64") (pin "G4") (pinfunction "VSS_G4") (pintype "power_in"))
      (node (ref "U64") (pin "G5") (pinfunction "VSS_G5") (pintype "power_in"))
      (node (ref "U64") (pin "G6") (pinfunction "VSS_G6") (pintype "power_in"))
      (node (ref "U64") (pin "H4") (pinfunction "VSS_H4") (pintype "power_in"))
      (node (ref "U64") (pin "H5") (pinfunction "VSS_H5") (pintype "power_in"))
      (node (ref "U64") (pin "H6") (pinfunction "VSS_H6") (pintype "power_in"))
      (node (ref "U64") (pin "H7") (pinfunction "VSS_H7") (pintype "power_in"))
      (node (ref "U64") (pin "J4") (pinfunction "VSS_J4") (pintype "power_in"))
      (node (ref "U64") (pin "J5") (pinfunction "VSS_J5") (pintype "power_in"))
      (node (ref "U64") (pin "J6") (pinfunction "VSS_J6") (pintype "power_in"))
      (node (ref "U64") (pin "K4") (pinfunction "VSS_K4") (pintype "power_in"))
      (node (ref "U64") (pin "K5") (pinfunction "VSS_K5") (pintype "power_in"))
      (node (ref "U64") (pin "K6") (pinfunction "VSS_K6") (pintype "power_in"))
      (node (ref "U64") (pin "L5") (pinfunction "VSS_L5") (pintype "power_in"))
      (node (ref "U64") (pin "L6") (pinfunction "VSSC_L6") (pintype "power_in"))
      (node (ref "U65") (pin "2") (pinfunction "GND_2") (pintype "power_in"))
      (node (ref "U66") (pin "2") (pinfunction "GND_2") (pintype "power_in"))
      (node (ref "Y7") (pin "2") (pinfunction "GND_2") (pintype "passive"))
    )
    (net (code "34") (name "Net-(C705-Pad1)") (class "Default")
      (node (ref "C705") (pin "1") (pinfunction "1_1") (pintype "passive"))
      (node (ref "R383") (pin "1") (pinfunction "1_1") (pintype "passive"))
      (node (ref "R384") (pin "1") (pinfunction "1_1") (pintype "passive"))
    )
    (net (code "35") (name "Net-(C706-Pad1)") (class "Default")
      (node (ref "C706") (pin "1") (pinfunction "1_1") (pintype "passive"))
      (node (ref "R385") (pin "1") (pinfunction "1_1") (pintype "passive"))
      (node (ref "R386") (pin "1") (pinfunction "1_1") (pintype "passive"))
    )
    (net (code "36") (name "Net-(C707-Pad1)") (class "Default")
      (node (ref "C707") (pin "1") (pinfunction "1_1") (pintype "passive"))
      (node (ref "R387") (pin "1") (pinfunction "1_1") (pintype "passive"))
      (node (ref "R388") (pin "1") (pinfunction "1_1") (pintype "passive"))
    )
    (net (code "37") (name "Net-(C708-Pad1)") (class "Default")
      (node (ref "C708") (pin "1") (pinfunction "1_1") (pintype "passive"))
      (node (ref "R389") (pin "1") (pinfunction "1_1") (pintype "passive"))
      (node (ref "R390") (pin "1") (pinfunction "1_1") (pintype "passive"))
    )
    (net (code "38") (name "Net-(DS9-K)") (class "Default")
      (node (ref "DS9") (pin "1") (pinfunction "K_1") (pintype "passive"))
      (node (ref "R407") (pin "2") (pinfunction "2_2") (pintype "passive"))
    )
    (net (code "39") (name "Net-(DS10-K)") (class "Default")
      (node (ref "DS10") (pin "1") (pinfunction "K_1") (pintype "passive"))
      (node (ref "R412") (pin "2") (pinfunction "2_2") (pintype "passive"))
    )
    (net (code "40") (name "Net-(DS11-K)") (class "Default")
      (node (ref "DS11") (pin "1") (pinfunction "K_1") (pintype "passive"))
      (node (ref "R415") (pin "2") (pinfunction "2_2") (pintype "passive"))
    )
    (net (code "41") (name "Net-(DS12-K)") (class "Default")
      (node (ref "DS12") (pin "1") (pinfunction "K_1") (pintype "passive"))
      (node (ref "R416") (pin "2") (pinfunction "2_2") (pintype "passive"))
    )
    (net (code "42") (name "Net-(U64A-RXD0)") (class "Default")
      (node (ref "TP31") (pin "1") (pinfunction "1_1") (pintype "passive"))
      (node (ref "U64") (pin "B2") (pinfunction "RXD0_B2") (pintype "output"))
    )
    (net (code "43") (name "Net-(U64A-RXD1)") (class "Default")
      (node (ref "TP32") (pin "1") (pinfunction "1_1") (pintype "passive"))
      (node (ref "U64") (pin "D3") (pinfunction "RXD1_D3") (pintype "output"))
    )
    (net (code "44") (name "Net-(U64A-RXD2)") (class "Default")
      (node (ref "TP33") (pin "1") (pinfunction "1_1") (pintype "passive"))
      (node (ref "U64") (pin "C3") (pinfunction "RXD2_C3") (pintype "output"))
    )
    (net (code "45") (name "Net-(U64A-RXD3)") (class "Default")
      (node (ref "TP34") (pin "1") (pinfunction "1_1") (pintype "passive"))
      (node (ref "U64") (pin "B3") (pinfunction "RXD3_B3") (pintype "output"))
    )
    (net (code "46") (name "Net-(U64B-COMA)") (class "Default")
      (node (ref "R400") (pin "2") (pinfunction "2_2") (pintype "passive"))
      (node (ref "U64") (pin "L4") (pinfunction "COMA_L4") (pintype "input"))
    )
    (net (code "47") (name "Net-(U64B-CONFIG[0])") (class "Default")
      (node (ref "R410") (pin "2") (pinfunction "2_2") (pintype "passive"))
      (node (ref "U64") (pin "D8") (pinfunction "CONFIG[0]_D8") (pintype "input"))
    )
    (net (code "48") (name "Net-(U64B-CONFIG[1])") (class "Default")
      (node (ref "R409") (pin "2") (pinfunction "2_2") (pintype "passive"))
      (node (ref "U64") (pin "E9") (pinfunction "CONFIG[1]_E9") (pintype "input"))
    )
    (net (code "49") (name "Net-(U64B-CONFIG[2])") (class "Default")
      (node (ref "R408") (pin "2") (pinfunction "2_2") (pintype "passive"))
      (node (ref "U64") (pin "F8") (pinfunction "CONFIG[2]_F8") (pintype "input"))
    )
    (net (code "50") (name "Net-(U64B-CONFIG[3])") (class "Default")
      (node (ref "R406") (pin "2") (pinfunction "2_2") (pintype "passive"))
      (node (ref "U64") (pin "G7") (pinfunction "CONFIG[3]_G7") (pintype "input"))
    )
    (net (code "51") (name "Net-(U64B-CONFIG[4])") (class "Default")
      (node (ref "R405") (pin "2") (pinfunction "2_2") (pintype "passive"))
      (node (ref "U64") (pin "F9") (pinfunction "CONFIG[4]_F9") (pintype "input"))
    )
    (net (code "52") (name "Net-(U64B-CONFIG[5])") (class "Default")
      (node (ref "R404") (pin "2") (pinfunction "2_2") (pintype "passive"))
      (node (ref "U64") (pin "G9") (pinfunction "CONFIG[5]_G9") (pintype "input"))
    )
    (net (code "53") (name "Net-(U64B-CONFIG[6])") (class "Default")
      (node (ref "R403") (pin "2") (pinfunction "2_2") (pintype "passive"))
      (node (ref "U64") (pin "G8") (pinfunction "CONFIG[6]_G8") (pintype "input"))
    )
    (net (code "54") (name "Net-(U64B-HSDAC+)") (class "Default")
      (node (ref "TP38") (pin "1") (pinfunction "1_1") (pintype "passive"))
      (node (ref "U64") (pin "M5") (pinfunction "HSDAC+_M5") (pintype "passive"))
    )
    (net (code "55") (name "Net-(U64B-HSDAC-)") (class "Default")
      (node (ref "TP37") (pin "1") (pinfunction "1_1") (pintype "passive"))
      (node (ref "U64") (pin "M6") (pinfunction "HSDAC-_M6") (pintype "passive"))
    )
    (net (code "56") (name "Net-(U64B-RESETn)") (class "Default")
      (node (ref "R402") (pin "2") (pinfunction "2_2") (pintype "passive"))
      (node (ref "U64") (pin "K3") (pinfunction "RESETn_K3") (pintype "input"))
    )
    (net (code "57") (name "Net-(U64B-RSET)") (class "Default")
      (node (ref "R414") (pin "2") (pinfunction "2_2") (pintype "passive"))
      (node (ref "U64") (pin "M2") (pinfunction "RSET_M2") (pintype "input"))
    )
    (net (code "58") (name "Net-(U64B-SEL_FREQ)") (class "Default")
      (node (ref "R413") (pin "2") (pinfunction "2_2") (pintype "passive"))
      (node (ref "U64") (pin "H8") (pinfunction "SEL_FREQ_H8") (pintype "input"))
    )
    (net (code "59") (name "Net-(U65-Y)") (class "Default")
      (node (ref "R391") (pin "1") (pinfunction "1_1") (pintype "passive"))
      (node (ref "U65") (pin "4") (pinfunction "Y_4") (pintype "output"))
    )
    (net (code "60") (name "Net-(U66-Y)") (class "Default")
      (node (ref "R396") (pin "1") (pinfunction "1_1") (pintype "passive"))
      (node (ref "U66") (pin "4") (pinfunction "Y_4") (pintype "output"))
    )
    (net (code "61") (name "Net-(Y7-EN)") (class "Default")
      (node (ref "R284") (pin "2") (pinfunction "2_2") (pintype "passive"))
      (node (ref "Y7") (pin "1") (pinfunction "EN_1") (pintype "passive"))
    )
    (net (code "62") (name "Net-(Y7-OUT)") (class "Default")
      (node (ref "R223") (pin "1") (pinfunction "1_1") (pintype "passive"))
      (node (ref "Y7") (pin "3") (pinfunction "OUT_3") (pintype "passive"))
    )
    (net (code "63") (name "V6NET_AVDD") (class "Default")
      (node (ref "C679") (pin "2") (pinfunction "2_2") (pintype "passive"))
      (node (ref "C680") (pin "2") (pinfunction "2_2") (pintype "passive"))
      (node (ref "C681") (pin "2") (pinfunction "2_2") (pintype "passive"))
      (node (ref "C682") (pin "2") (pinfunction "2_2") (pintype "passive"))
      (node (ref "C683") (pin "2") (pinfunction "2_2") (pintype "passive"))
      (node (ref "C684") (pin "2") (pinfunction "2_2") (pintype "passive"))
      (node (ref "L24") (pin "2") (pinfunction "2_2") (pintype "passive"))
      (node (ref "U64") (pin "B7") (pinfunction "AVDD_B7") (pintype "power_in"))
      (node (ref "U64") (pin "M3") (pinfunction "AVDD_M3") (pintype "power_in"))
      (node (ref "U64") (pin "M4") (pinfunction "AVDD_M4") (pintype "power_in"))
      (node (ref "U64") (pin "M7") (pinfunction "AVDD_M7") (pintype "power_in"))
      (node (ref "U64") (pin "M8") (pinfunction "AVDD_M8") (pintype "power_in"))
      (node (ref "U64") (pin "N5") (pinfunction "AVDD_N5") (pintype "power_in"))
    )
    (net (code "64") (name "unconnected-(P12-MNT1-Pad15)") (class "Default")
      (node (ref "P12") (pin "15") (pinfunction "MNT1_15") (pintype "passive+no_connect"))
    )
    (net (code "65") (name "unconnected-(P12-MNT2-Pad16)") (class "Default")
      (node (ref "P12") (pin "16") (pinfunction "MNT2_16") (pintype "passive+no_connect"))
    )
    (net (code "66") (name "unconnected-(U64A-125CLK-PadK2)") (class "Default")
      (node (ref "U64") (pin "K2") (pinfunction "125CLK_K2") (pintype "output+no_connect"))
    )
    (net (code "67") (name "unconnected-(U64A-COL-PadB6)") (class "Default")
      (node (ref "U64") (pin "B6") (pinfunction "COL_B6") (pintype "output+no_connect"))
    )
    (net (code "68") (name "unconnected-(U64A-CRS-PadB5)") (class "Default")
      (node (ref "U64") (pin "B5") (pinfunction "CRS_B5") (pintype "output+no_connect"))
    )
    (net (code "69") (name "unconnected-(U64A-GTX_CLK-PadE2)") (class "Default")
      (node (ref "U64") (pin "E2") (pinfunction "GTX_CLK_E2") (pintype "input+no_connect"))
    )
    (net (code "70") (name "unconnected-(U64A-RXD4-PadC4)") (class "Default")
      (node (ref "U64") (pin "C4") (pinfunction "RXD4_C4") (pintype "output+no_connect"))
    )
    (net (code "71") (name "unconnected-(U64A-RXD5-PadA1)") (class "Default")
      (node (ref "U64") (pin "A1") (pinfunction "RXD5_A1") (pintype "output+no_connect"))
    )
    (net (code "72") (name "unconnected-(U64A-RXD6-PadA2)") (class "Default")
      (node (ref "U64") (pin "A2") (pinfunction "RXD6_A2") (pintype "output+no_connect"))
    )
    (net (code "73") (name "unconnected-(U64A-RXD7-PadC5)") (class "Default")
      (node (ref "U64") (pin "C5") (pinfunction "RXD7_C5") (pintype "output+no_connect"))
    )
    (net (code "74") (name "unconnected-(U64A-RX_CLK-PadC1)") (class "Default")
      (node (ref "U64") (pin "C1") (pinfunction "RX_CLK_C1") (pintype "output+no_connect"))
    )
    (net (code "75") (name "unconnected-(U64A-RX_DV-PadB1)") (class "Default")
      (node (ref "U64") (pin "B1") (pinfunction "RX_DV_B1") (pintype "output+no_connect"))
    )
    (net (code "76") (name "unconnected-(U64A-RX_ER-PadD2)") (class "Default")
      (node (ref "U64") (pin "D2") (pinfunction "RX_ER_D2") (pintype "output+no_connect"))
    )
    (net (code "77") (name "unconnected-(U64A-S_CLK+-PadA5)") (class "Default")
      (node (ref "U64") (pin "A5") (pinfunction "S_CLK+_A5") (pintype "input+no_connect"))
    )
    (net (code "78") (name "unconnected-(U64A-S_CLK--PadA6)") (class "Default")
      (node (ref "U64") (pin "A6") (pinfunction "S_CLK-_A6") (pintype "input+no_connect"))
    )
    (net (code "79") (name "unconnected-(U64A-TXD0-PadF1)") (class "Default")
      (node (ref "U64") (pin "F1") (pinfunction "TXD0_F1") (pintype "input+no_connect"))
    )
    (net (code "80") (name "unconnected-(U64A-TXD1-PadG2)") (class "Default")
      (node (ref "U64") (pin "G2") (pinfunction "TXD1_G2") (pintype "input+no_connect"))
    )
    (net (code "81") (name "unconnected-(U64A-TXD2-PadG3)") (class "Default")
      (node (ref "U64") (pin "G3") (pinfunction "TXD2_G3") (pintype "input+no_connect"))
    )
    (net (code "82") (name "unconnected-(U64A-TXD3-PadH2)") (class "Default")
      (node (ref "U64") (pin "H2") (pinfunction "TXD3_H2") (pintype "input+no_connect"))
    )
    (net (code "83") (name "unconnected-(U64A-TXD4-PadH1)") (class "Default")
      (node (ref "U64") (pin "H1") (pinfunction "TXD4_H1") (pintype "input+no_connect"))
    )
    (net (code "84") (name "unconnected-(U64A-TXD5-PadH3)") (class "Default")
      (node (ref "U64") (pin "H3") (pinfunction "TXD5_H3") (pintype "input+no_connect"))
    )
    (net (code "85") (name "unconnected-(U64A-TXD6-PadJ1)") (class "Default")
      (node (ref "U64") (pin "J1") (pinfunction "TXD6_J1") (pintype "input+no_connect"))
    )
    (net (code "86") (name "unconnected-(U64A-TXD7-PadJ2)") (class "Default")
      (node (ref "U64") (pin "J2") (pinfunction "TXD7_J2") (pintype "input+no_connect"))
    )
    (net (code "87") (name "unconnected-(U64A-TX_CLK-PadD1)") (class "Default")
      (node (ref "U64") (pin "D1") (pinfunction "TX_CLK_D1") (pintype "output+no_connect"))
    )
    (net (code "88") (name "unconnected-(U64A-TX_EN-PadE1)") (class "Default")
      (node (ref "U64") (pin "E1") (pinfunction "TX_EN_E1") (pintype "input+no_connect"))
    )
    (net (code "89") (name "unconnected-(U64A-TX_ER-PadF2)") (class "Default")
      (node (ref "U64") (pin "F2") (pinfunction "TX_ER_F2") (pintype "input+no_connect"))
    )
    (net (code "90") (name "unconnected-(U64B-INTn-PadL1)") (class "Default")
      (node (ref "U64") (pin "L1") (pinfunction "INTn_L1") (pintype "input+no_connect"))
    )
    (net (code "91") (name "unconnected-(U64B-NC-PadG1)") (class "Default")
      (node (ref "U64") (pin "G1") (pinfunction "NC_G1") (pintype "passive+no_connect"))
    )
    (net (code "92") (name "unconnected-(U64B-NC-PadK7)") (class "Default")
      (node (ref "U64") (pin "K7") (pinfunction "NC_K7") (pintype "passive+no_connect"))
    )
    (net (code "93") (name "unconnected-(U64B-XTAL2-PadJ9)") (class "Default")
      (node (ref "U64") (pin "J9") (pinfunction "XTAL2_J9") (pintype "input+no_connect"))
    )
    (net (code "94") (name "unconnected-(U64C-TRSTn-PadM9)") (class "Default")
      (node (ref "U64") (pin "M9") (pinfunction "TRSTn_M9") (pintype "input+no_connect"))
    )
  )
)
